# PCB-TLY-JACK-MEGA.net
KiCad netlist of a schematic drawn in EAGLE
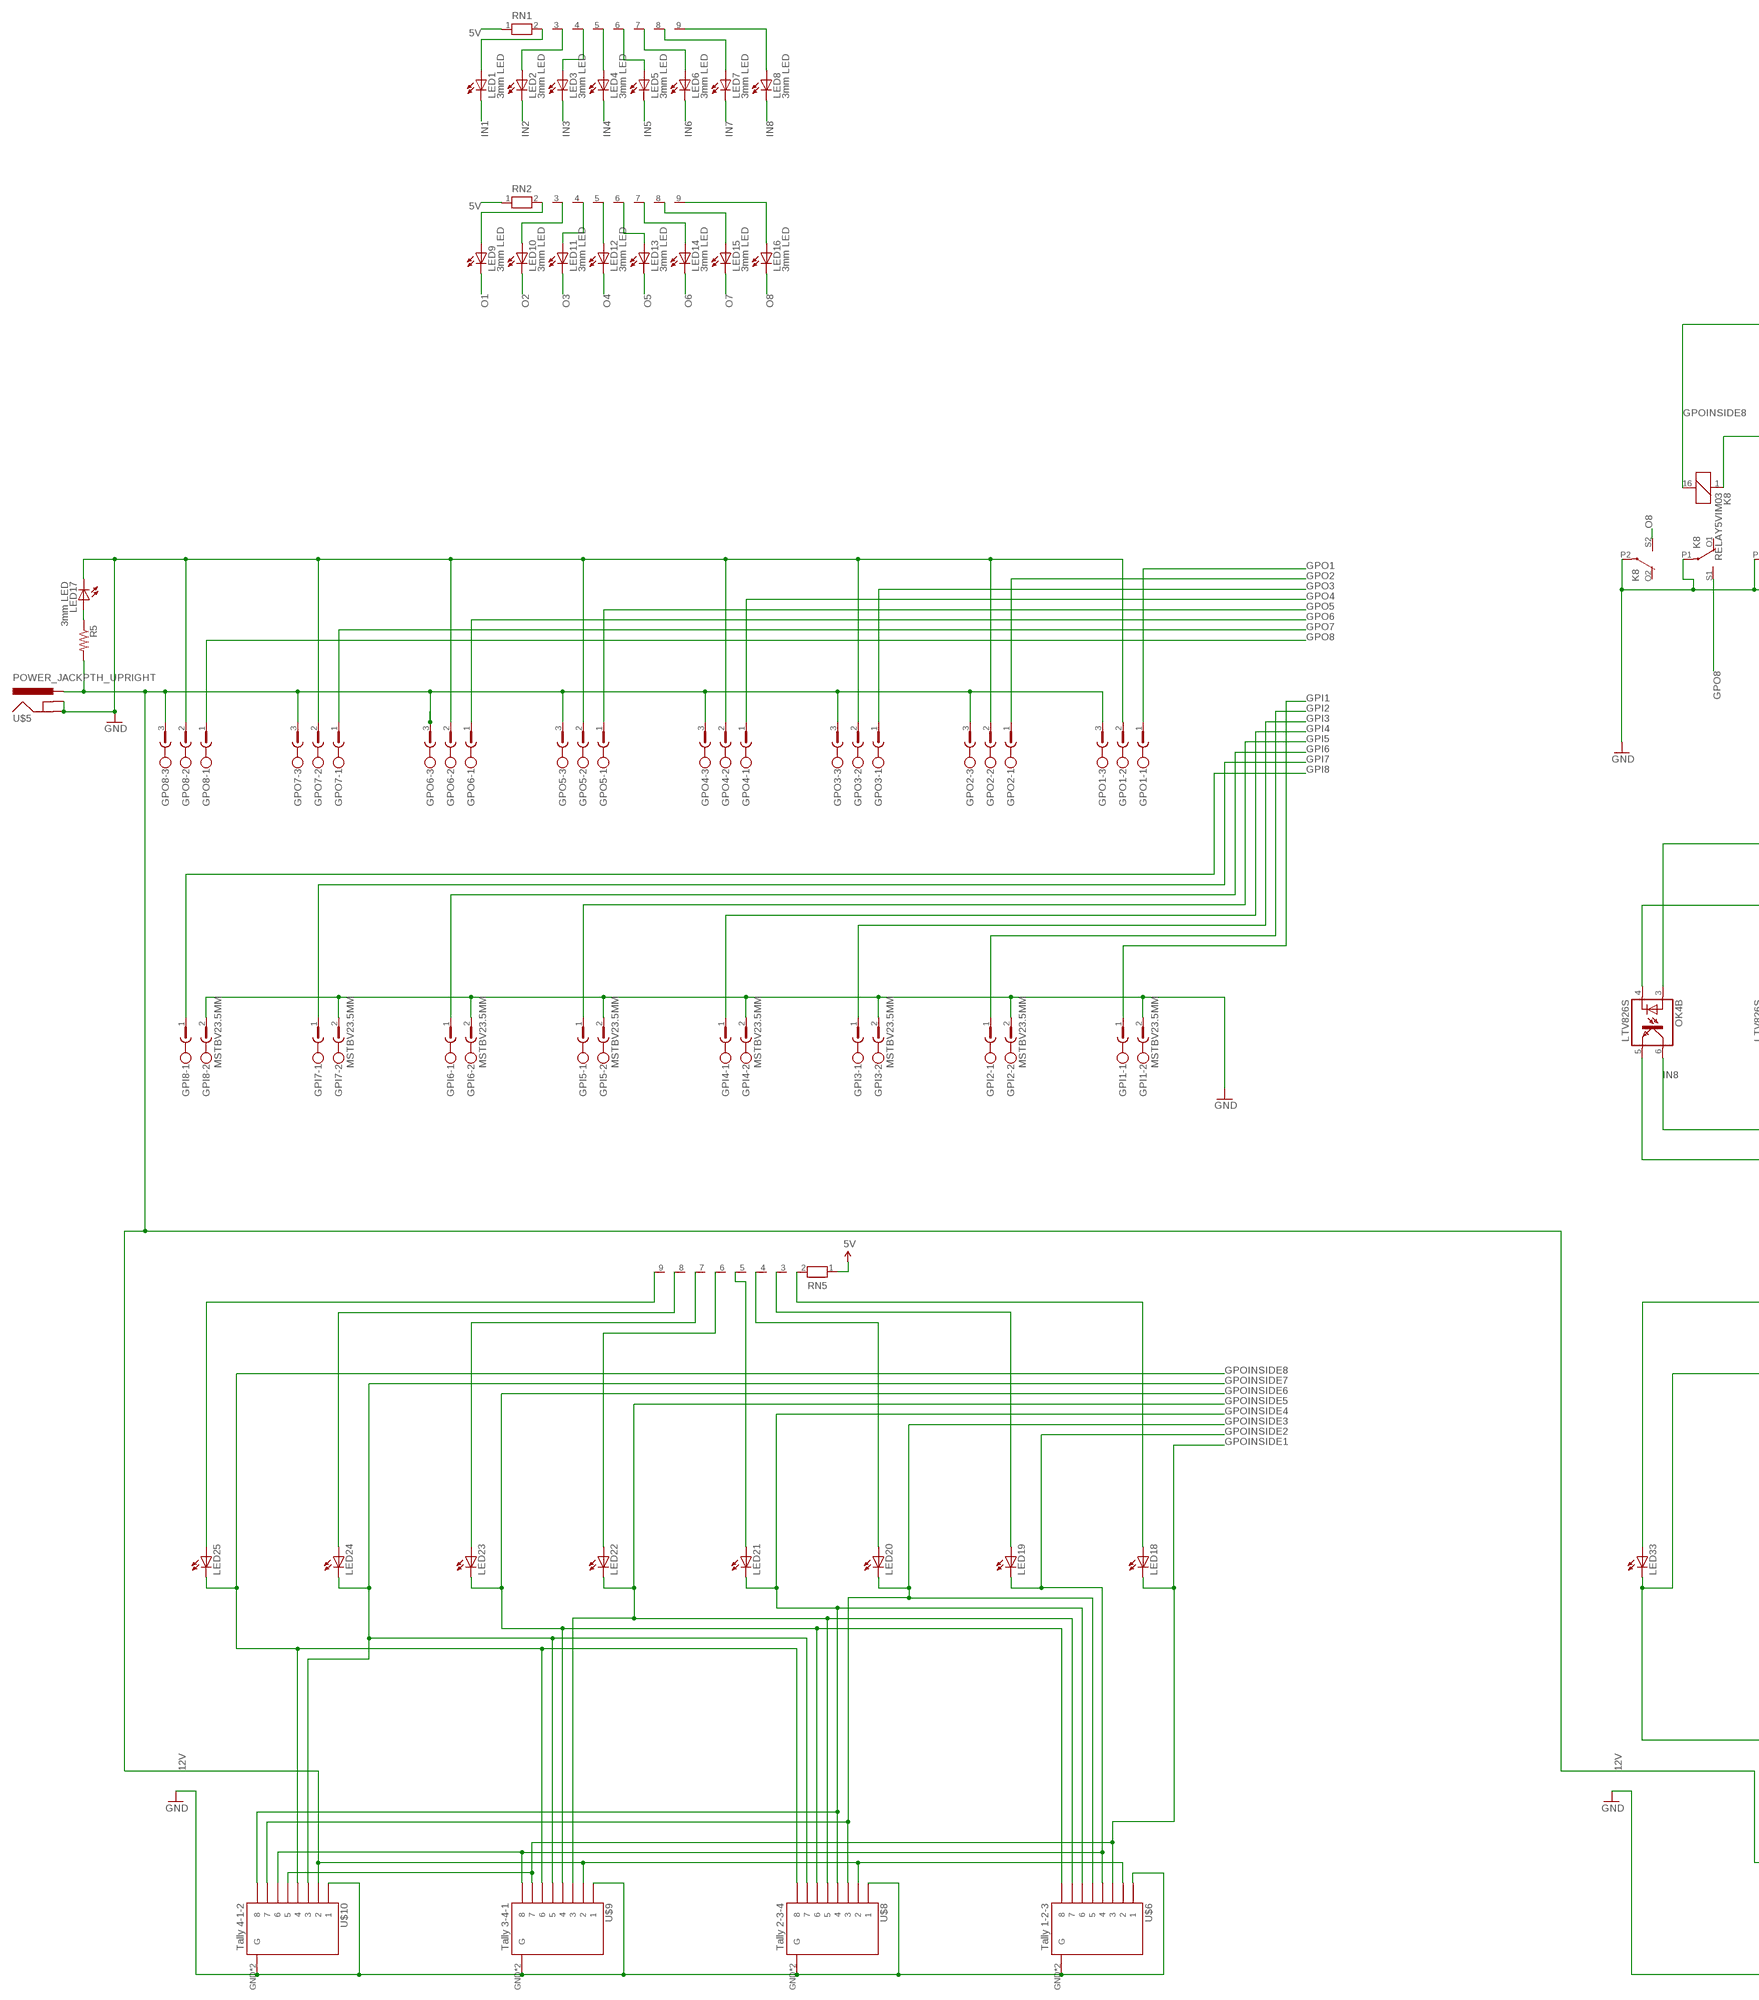
[diagram p0: schematic, sheet 1, part 1 of 2]
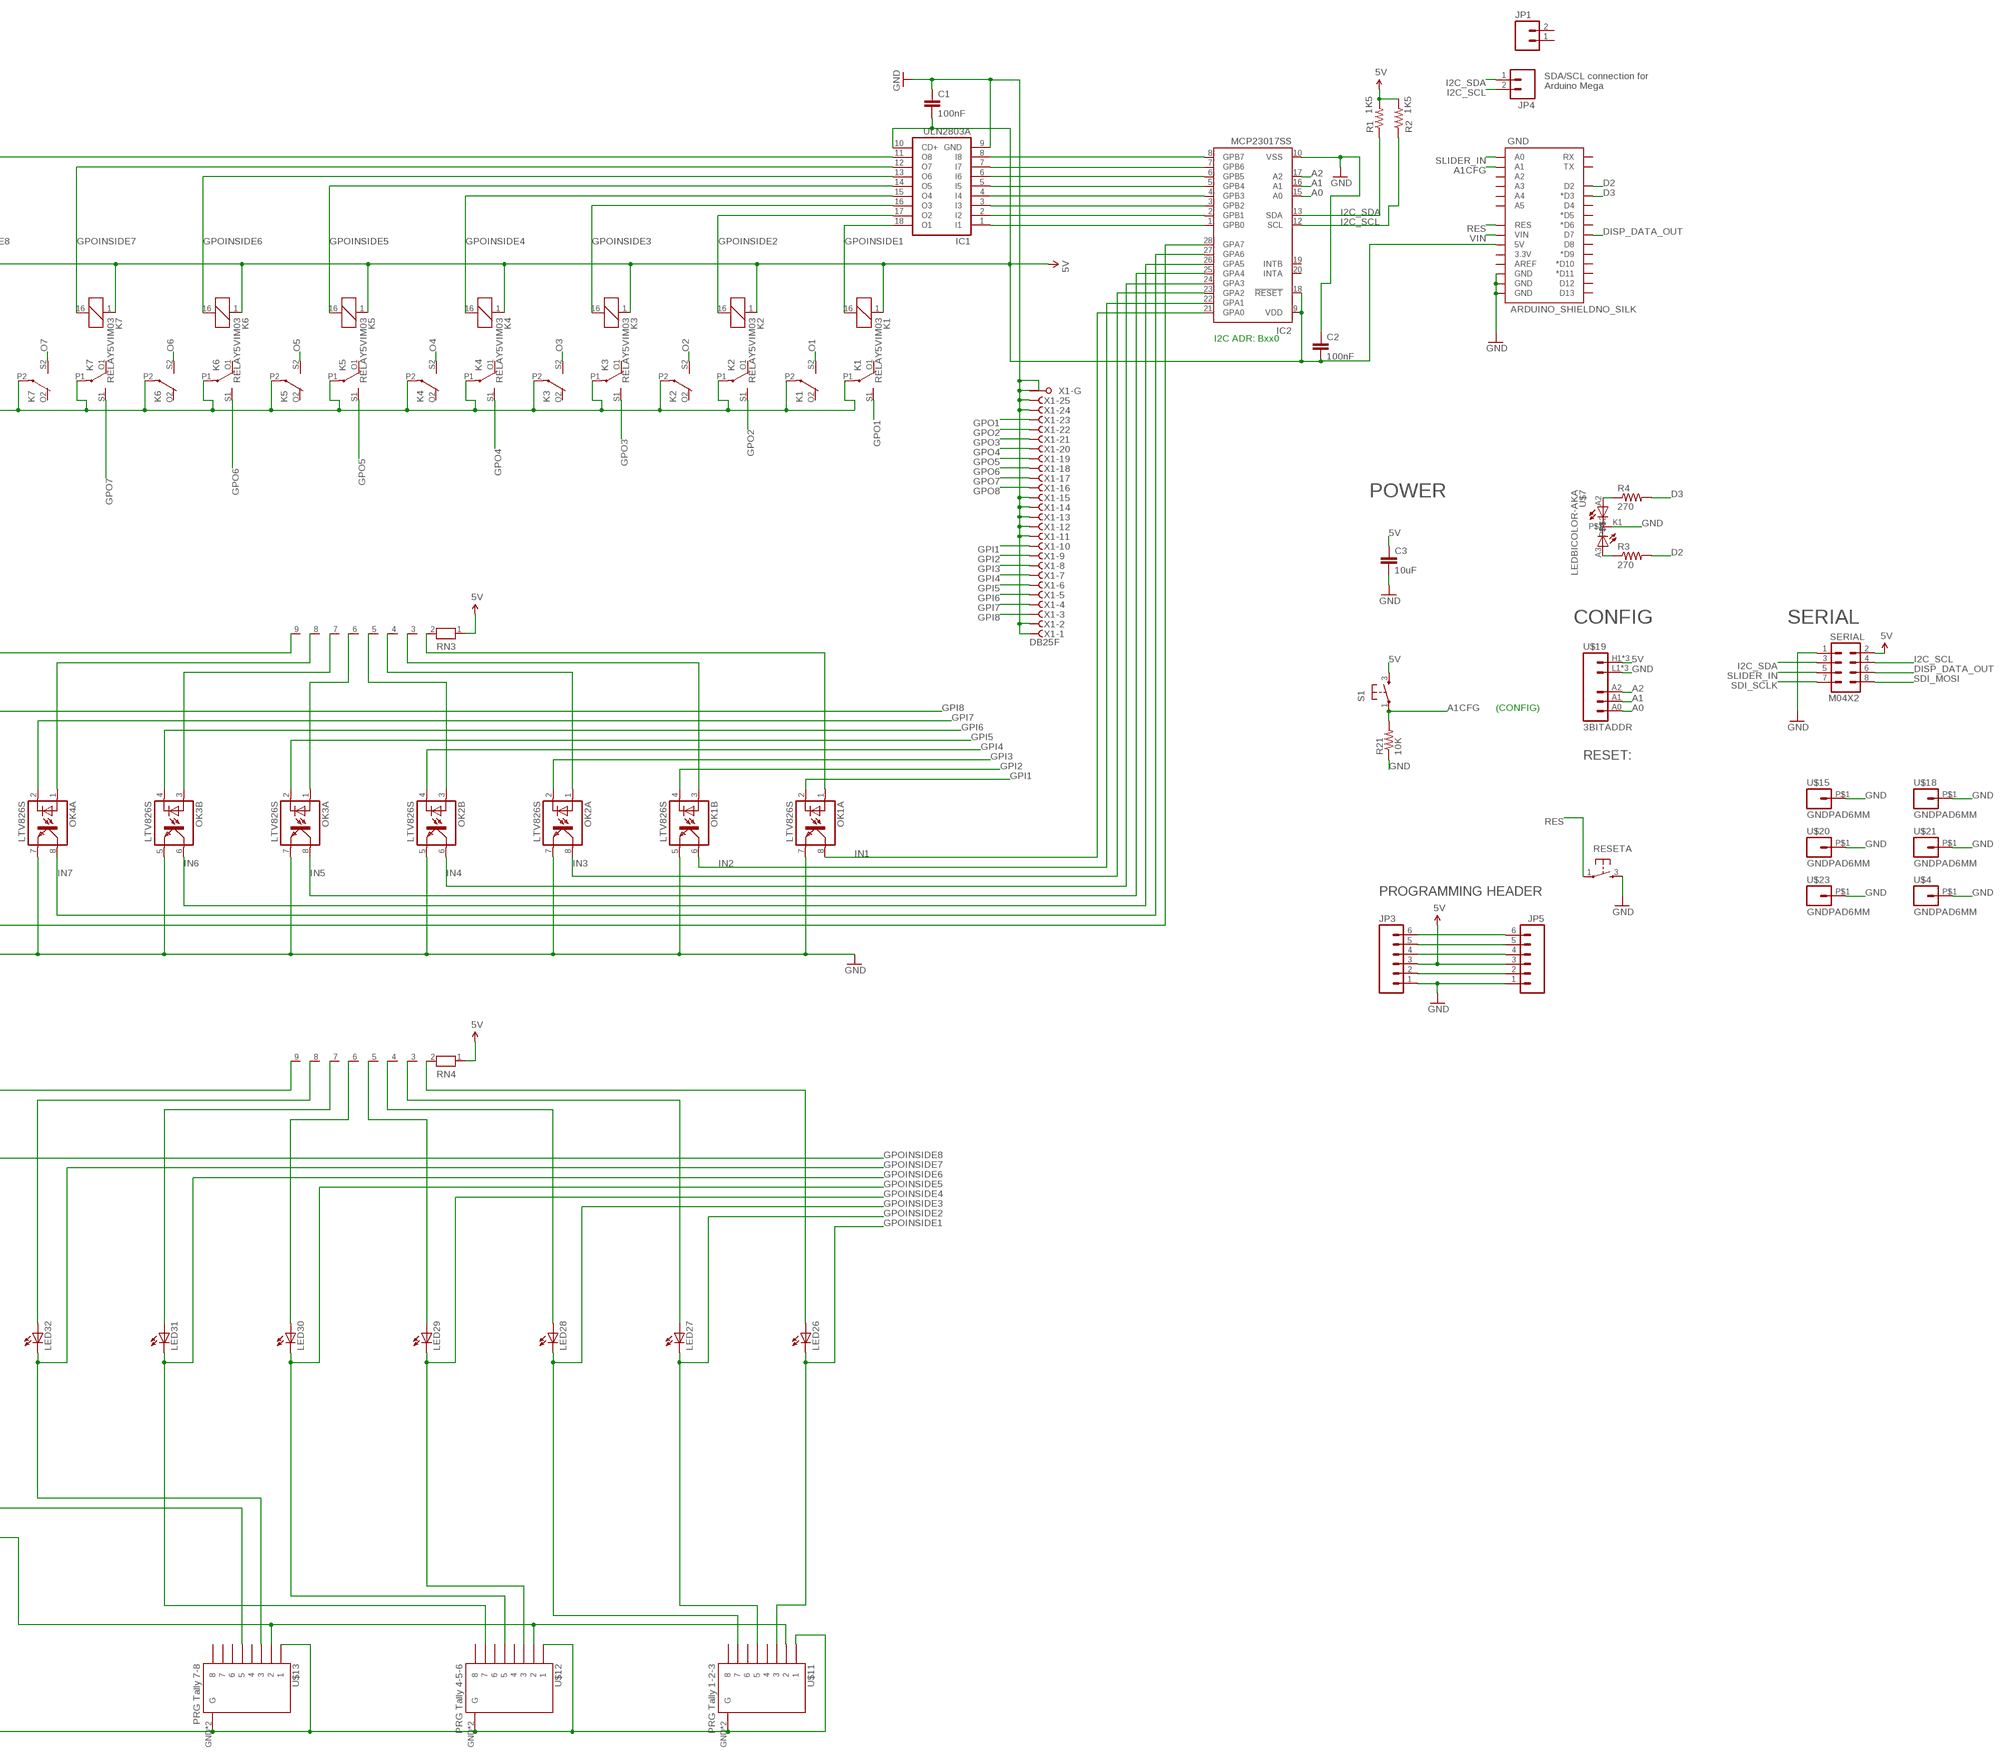
[diagram p1: schematic, sheet 1, part 2 of 2]

(export (version "E")
  (design (tool "Eeschema 10.0.6"))
  (components
    (comp (ref "C1")
      (value "100nF")
      (footprint "eagle-import:0805")
      (libsource (lib "eagle-import") (part "CAP0805"))
    )
    (comp (ref "C2")
      (value "100nF")
      (footprint "eagle-import:0603-CAP")
      (libsource (lib "eagle-import") (part "CAP0603-CAP"))
    )
    (comp (ref "C3")
      (value "10uF")
      (footprint "eagle-import:0805")
      (libsource (lib "eagle-import") (part "CAP0805"))
    )
    (comp (ref "GND")
      (value "ARDUINO_SHIELDNO_SILK")
      (footprint "eagle-import:DUEMILANOVE_VIAS")
      (libsource (lib "eagle-import") (part "ARDUINO_SHIELDNO_SILK"))
    )
    (comp (ref "GPI1")
      (value "MSTBV23.5MM")
      (footprint "eagle-import:MSTBV2-3.5")
      (libsource (lib "eagle-import") (part "MSTBV23.5MM"))
    )
    (comp (ref "GPI2")
      (value "MSTBV23.5MM")
      (footprint "eagle-import:MSTBV2-3.5")
      (libsource (lib "eagle-import") (part "MSTBV23.5MM"))
    )
    (comp (ref "GPI3")
      (value "MSTBV23.5MM")
      (footprint "eagle-import:MSTBV2-3.5")
      (libsource (lib "eagle-import") (part "MSTBV23.5MM"))
    )
    (comp (ref "GPI4")
      (value "MSTBV23.5MM")
      (footprint "eagle-import:MSTBV2-3.5")
      (libsource (lib "eagle-import") (part "MSTBV23.5MM"))
    )
    (comp (ref "GPI5")
      (value "MSTBV23.5MM")
      (footprint "eagle-import:MSTBV2-3.5")
      (libsource (lib "eagle-import") (part "MSTBV23.5MM"))
    )
    (comp (ref "GPI6")
      (value "MSTBV23.5MM")
      (footprint "eagle-import:MSTBV2-3.5")
      (libsource (lib "eagle-import") (part "MSTBV23.5MM"))
    )
    (comp (ref "GPI7")
      (value "MSTBV23.5MM")
      (footprint "eagle-import:MSTBV2-3.5")
      (libsource (lib "eagle-import") (part "MSTBV23.5MM"))
    )
    (comp (ref "GPI8")
      (value "MSTBV23.5MM")
      (footprint "eagle-import:MSTBV2-3.5")
      (libsource (lib "eagle-import") (part "MSTBV23.5MM"))
    )
    (comp (ref "GPO1")
      (value "CON1")
      (footprint "eagle-import:MSTBV3-3.5")
      (libsource (lib "eagle-import") (part "MSTBV33.5MM"))
    )
    (comp (ref "GPO2")
      (value "CON1")
      (footprint "eagle-import:MSTBV3-3.5")
      (libsource (lib "eagle-import") (part "MSTBV33.5MM"))
    )
    (comp (ref "GPO3")
      (value "CON1")
      (footprint "eagle-import:MSTBV3-3.5")
      (libsource (lib "eagle-import") (part "MSTBV33.5MM"))
    )
    (comp (ref "GPO4")
      (value "CON1")
      (footprint "eagle-import:MSTBV3-3.5")
      (libsource (lib "eagle-import") (part "MSTBV33.5MM"))
    )
    (comp (ref "GPO5")
      (value "CON1")
      (footprint "eagle-import:MSTBV3-3.5")
      (libsource (lib "eagle-import") (part "MSTBV33.5MM"))
    )
    (comp (ref "GPO6")
      (value "CON1")
      (footprint "eagle-import:MSTBV3-3.5")
      (libsource (lib "eagle-import") (part "MSTBV33.5MM"))
    )
    (comp (ref "GPO7")
      (value "CON1")
      (footprint "eagle-import:MSTBV3-3.5")
      (libsource (lib "eagle-import") (part "MSTBV33.5MM"))
    )
    (comp (ref "GPO8")
      (value "CON1")
      (footprint "eagle-import:MSTBV3-3.5")
      (libsource (lib "eagle-import") (part "MSTBV33.5MM"))
    )
    (comp (ref "IC1")
      (value "ULN2803A")
      (footprint "eagle-import:SO18W")
      (libsource (lib "eagle-import") (part "ULN2803ASO18W"))
    )
    (comp (ref "IC2")
      (value "MCP23017SS")
      (footprint "eagle-import:SSOP28")
      (fields (field (name "MF") "MICROCHIP") (field (name "MPN") "MCP23017-E/SS"))
      (libsource (lib "eagle-import") (part "MCP23017SS"))
    )
    (comp (ref "JP1")
      (value "M02PTH")
      (footprint "eagle-import:1X02")
      (libsource (lib "eagle-import") (part "M02PTH"))
    )
    (comp (ref "JP3")
      (value "M06POLAR")
      (footprint "eagle-import:MOLEX-1X6")
      (libsource (lib "eagle-import") (part "M06POLAR"))
    )
    (comp (ref "JP4")
      (value "M02PTH")
      (footprint "eagle-import:1X02")
      (libsource (lib "eagle-import") (part "M02PTH"))
    )
    (comp (ref "JP5")
      (value "M06POLAR")
      (footprint "eagle-import:MOLEX-1X6")
      (libsource (lib "eagle-import") (part "M06POLAR"))
    )
    (comp (ref "K1")
      (value "RELAY5VIM03")
      (footprint "eagle-import:DS2Y")
      (libsource (lib "eagle-import") (part "RELAY5VIM03"))
    )
    (comp (ref "K2")
      (value "RELAY5VIM03")
      (footprint "eagle-import:DS2Y")
      (libsource (lib "eagle-import") (part "RELAY5VIM03"))
    )
    (comp (ref "K3")
      (value "RELAY5VIM03")
      (footprint "eagle-import:DS2Y")
      (libsource (lib "eagle-import") (part "RELAY5VIM03"))
    )
    (comp (ref "K4")
      (value "RELAY5VIM03")
      (footprint "eagle-import:DS2Y")
      (libsource (lib "eagle-import") (part "RELAY5VIM03"))
    )
    (comp (ref "K5")
      (value "RELAY5VIM03")
      (footprint "eagle-import:DS2Y")
      (libsource (lib "eagle-import") (part "RELAY5VIM03"))
    )
    (comp (ref "K6")
      (value "RELAY5VIM03")
      (footprint "eagle-import:DS2Y")
      (libsource (lib "eagle-import") (part "RELAY5VIM03"))
    )
    (comp (ref "K7")
      (value "RELAY5VIM03")
      (footprint "eagle-import:DS2Y")
      (libsource (lib "eagle-import") (part "RELAY5VIM03"))
    )
    (comp (ref "K8")
      (value "RELAY5VIM03")
      (footprint "eagle-import:DS2Y")
      (libsource (lib "eagle-import") (part "RELAY5VIM03"))
    )
    (comp (ref "LED1")
      (value "3mm LED")
      (footprint "eagle-import:LED3MM")
      (libsource (lib "eagle-import") (part "LED3MM"))
    )
    (comp (ref "LED2")
      (value "3mm LED")
      (footprint "eagle-import:LED3MM")
      (libsource (lib "eagle-import") (part "LED3MM"))
    )
    (comp (ref "LED3")
      (value "3mm LED")
      (footprint "eagle-import:LED3MM")
      (libsource (lib "eagle-import") (part "LED3MM"))
    )
    (comp (ref "LED4")
      (value "3mm LED")
      (footprint "eagle-import:LED3MM")
      (libsource (lib "eagle-import") (part "LED3MM"))
    )
    (comp (ref "LED5")
      (value "3mm LED")
      (footprint "eagle-import:LED3MM")
      (libsource (lib "eagle-import") (part "LED3MM"))
    )
    (comp (ref "LED6")
      (value "3mm LED")
      (footprint "eagle-import:LED3MM")
      (libsource (lib "eagle-import") (part "LED3MM"))
    )
    (comp (ref "LED7")
      (value "3mm LED")
      (footprint "eagle-import:LED3MM")
      (libsource (lib "eagle-import") (part "LED3MM"))
    )
    (comp (ref "LED8")
      (value "3mm LED")
      (footprint "eagle-import:LED3MM")
      (libsource (lib "eagle-import") (part "LED3MM"))
    )
    (comp (ref "LED9")
      (value "3mm LED")
      (footprint "eagle-import:LED3MM")
      (libsource (lib "eagle-import") (part "LED3MM"))
    )
    (comp (ref "LED10")
      (value "3mm LED")
      (footprint "eagle-import:LED3MM")
      (libsource (lib "eagle-import") (part "LED3MM"))
    )
    (comp (ref "LED11")
      (value "3mm LED")
      (footprint "eagle-import:LED3MM")
      (libsource (lib "eagle-import") (part "LED3MM"))
    )
    (comp (ref "LED12")
      (value "3mm LED")
      (footprint "eagle-import:LED3MM")
      (libsource (lib "eagle-import") (part "LED3MM"))
    )
    (comp (ref "LED13")
      (value "3mm LED")
      (footprint "eagle-import:LED3MM")
      (libsource (lib "eagle-import") (part "LED3MM"))
    )
    (comp (ref "LED14")
      (value "3mm LED")
      (footprint "eagle-import:LED3MM")
      (libsource (lib "eagle-import") (part "LED3MM"))
    )
    (comp (ref "LED15")
      (value "3mm LED")
      (footprint "eagle-import:LED3MM")
      (libsource (lib "eagle-import") (part "LED3MM"))
    )
    (comp (ref "LED16")
      (value "3mm LED")
      (footprint "eagle-import:LED3MM")
      (libsource (lib "eagle-import") (part "LED3MM"))
    )
    (comp (ref "LED17")
      (value "3mm LED")
      (footprint "eagle-import:LED3MM")
      (libsource (lib "eagle-import") (part "LED3MM"))
    )
    (comp (ref "LED18")
      (value "LED3MM")
      (footprint "eagle-import:LED3MM")
      (libsource (lib "eagle-import") (part "led_LED3MM"))
    )
    (comp (ref "LED19")
      (value "LED3MM")
      (footprint "eagle-import:LED3MM")
      (libsource (lib "eagle-import") (part "led_LED3MM"))
    )
    (comp (ref "LED20")
      (value "LED3MM")
      (footprint "eagle-import:LED3MM")
      (libsource (lib "eagle-import") (part "led_LED3MM"))
    )
    (comp (ref "LED21")
      (value "LED3MM")
      (footprint "eagle-import:LED3MM")
      (libsource (lib "eagle-import") (part "led_LED3MM"))
    )
    (comp (ref "LED22")
      (value "LED3MM")
      (footprint "eagle-import:LED3MM")
      (libsource (lib "eagle-import") (part "led_LED3MM"))
    )
    (comp (ref "LED23")
      (value "LED3MM")
      (footprint "eagle-import:LED3MM")
      (libsource (lib "eagle-import") (part "led_LED3MM"))
    )
    (comp (ref "LED24")
      (value "LED3MM")
      (footprint "eagle-import:LED3MM")
      (libsource (lib "eagle-import") (part "led_LED3MM"))
    )
    (comp (ref "LED25")
      (value "LED3MM")
      (footprint "eagle-import:LED3MM")
      (libsource (lib "eagle-import") (part "led_LED3MM"))
    )
    (comp (ref "LED26")
      (value "LED3MM")
      (footprint "eagle-import:LED3MM")
      (libsource (lib "eagle-import") (part "led_LED3MM"))
    )
    (comp (ref "LED27")
      (value "LED3MM")
      (footprint "eagle-import:LED3MM")
      (libsource (lib "eagle-import") (part "led_LED3MM"))
    )
    (comp (ref "LED28")
      (value "LED3MM")
      (footprint "eagle-import:LED3MM")
      (libsource (lib "eagle-import") (part "led_LED3MM"))
    )
    (comp (ref "LED29")
      (value "LED3MM")
      (footprint "eagle-import:LED3MM")
      (libsource (lib "eagle-import") (part "led_LED3MM"))
    )
    (comp (ref "LED30")
      (value "LED3MM")
      (footprint "eagle-import:LED3MM")
      (libsource (lib "eagle-import") (part "led_LED3MM"))
    )
    (comp (ref "LED31")
      (value "LED3MM")
      (footprint "eagle-import:LED3MM")
      (libsource (lib "eagle-import") (part "led_LED3MM"))
    )
    (comp (ref "LED32")
      (value "LED3MM")
      (footprint "eagle-import:LED3MM")
      (libsource (lib "eagle-import") (part "led_LED3MM"))
    )
    (comp (ref "LED33")
      (value "LED3MM")
      (footprint "eagle-import:LED3MM")
      (libsource (lib "eagle-import") (part "led_LED3MM"))
    )
    (comp (ref "OK1")
      (value "LTV826S")
      (footprint "eagle-import:DIL8-SMD")
      (libsource (lib "eagle-import") (part "LTV826S"))
    )
    (comp (ref "OK2")
      (value "LTV826S")
      (footprint "eagle-import:DIL8-SMD")
      (libsource (lib "eagle-import") (part "LTV826S"))
    )
    (comp (ref "OK3")
      (value "LTV826S")
      (footprint "eagle-import:DIL8-SMD")
      (libsource (lib "eagle-import") (part "LTV826S"))
    )
    (comp (ref "OK4")
      (value "LTV826S")
      (footprint "eagle-import:DIL8-SMD")
      (libsource (lib "eagle-import") (part "LTV826S"))
    )
    (comp (ref "R1")
      (value "1K5")
      (footprint "eagle-import:0603-RES")
      (libsource (lib "eagle-import") (part "RESISTOR0603-RES"))
    )
    (comp (ref "R2")
      (value "1K5")
      (footprint "eagle-import:0603-RES")
      (libsource (lib "eagle-import") (part "RESISTOR0603-RES"))
    )
    (comp (ref "R3")
      (value "270")
      (footprint "eagle-import:0603-RES")
      (libsource (lib "eagle-import") (part "RESISTOR0603-RES"))
    )
    (comp (ref "R4")
      (value "270")
      (footprint "eagle-import:0603-RES")
      (libsource (lib "eagle-import") (part "RESISTOR0603-RES"))
    )
    (comp (ref "R5")
      (value "RESISTOR0603-RES")
      (footprint "eagle-import:0603-RES")
      (libsource (lib "eagle-import") (part "RESISTOR0603-RES"))
    )
    (comp (ref "R21")
      (value "10K")
      (footprint "eagle-import:0603-RES")
      (libsource (lib "eagle-import") (part "RESISTOR0603-RES"))
    )
    (comp (ref "RESETA")
      (value "TAC_SWITCH")
      (footprint "eagle-import:PUSHBUTTON")
      (libsource (lib "eagle-import") (part "TAC_SWITCH"))
    )
    (comp (ref "RN1")
      (value "RN08")
      (footprint "eagle-import:RN-9")
      (libsource (lib "eagle-import") (part "RN08"))
    )
    (comp (ref "RN2")
      (value "RN08")
      (footprint "eagle-import:RN-9")
      (libsource (lib "eagle-import") (part "RN08"))
    )
    (comp (ref "RN3")
      (value "RN08")
      (footprint "eagle-import:RN-9")
      (libsource (lib "eagle-import") (part "RN08"))
    )
    (comp (ref "RN4")
      (value "RN08")
      (footprint "eagle-import:RN-9")
      (libsource (lib "eagle-import") (part "RN08"))
    )
    (comp (ref "RN5")
      (value "RN08")
      (footprint "eagle-import:RN-9")
      (libsource (lib "eagle-import") (part "RN08"))
    )
    (comp (ref "S1")
      (value "TAC_SWITCH")
      (footprint "eagle-import:PUSHBUTTON")
      (libsource (lib "eagle-import") (part "TAC_SWITCH"))
    )
    (comp (ref "SERIAL")
      (value "M04X2")
      (footprint "eagle-import:2X4")
      (libsource (lib "eagle-import") (part "M04X2"))
    )
    (comp (ref "U$4")
      (value "GNDPAD6MM")
      (footprint "eagle-import:3.2MMPAD6MM")
      (libsource (lib "eagle-import") (part "GNDPAD6MM"))
    )
    (comp (ref "U$5")
      (value "POWER_JACKPTH_UPRIGHT")
      (footprint "eagle-import:POWER_JACK_PTH_UPRIGHT")
      (libsource (lib "eagle-import") (part "POWER_JACKPTH_UPRIGHT"))
    )
    (comp (ref "U$6")
      (value "Tally 1-2-3")
      (footprint "eagle-import:RJ45-8_GND_UPRIGHT")
      (libsource (lib "eagle-import") (part "RJ45-8_GNDUPRIGHT"))
    )
    (comp (ref "U$7")
      (value "LEDBICOLOR-AKA")
      (footprint "eagle-import:LED5MM-BICOLOR")
      (libsource (lib "eagle-import") (part "LEDBICOLOR-AKA"))
    )
    (comp (ref "U$8")
      (value "Tally 2-3-4")
      (footprint "eagle-import:RJ45-8_GND_UPRIGHT")
      (libsource (lib "eagle-import") (part "RJ45-8_GNDUPRIGHT"))
    )
    (comp (ref "U$9")
      (value "Tally 3-4-1")
      (footprint "eagle-import:RJ45-8_GND_UPRIGHT")
      (libsource (lib "eagle-import") (part "RJ45-8_GNDUPRIGHT"))
    )
    (comp (ref "U$10")
      (value "Tally 4-1-2")
      (footprint "eagle-import:RJ45-8_GND_UPRIGHT")
      (libsource (lib "eagle-import") (part "RJ45-8_GNDUPRIGHT"))
    )
    (comp (ref "U$11")
      (value "PRG Tally 1-2-3")
      (footprint "eagle-import:RJ45-8_GND_UPRIGHT")
      (libsource (lib "eagle-import") (part "RJ45-8_GNDUPRIGHT"))
    )
    (comp (ref "U$12")
      (value "PRG Tally 4-5-6")
      (footprint "eagle-import:RJ45-8_GND_UPRIGHT")
      (libsource (lib "eagle-import") (part "RJ45-8_GNDUPRIGHT"))
    )
    (comp (ref "U$13")
      (value "PRG Tally 7-8")
      (footprint "eagle-import:RJ45-8_GND_UPRIGHT")
      (libsource (lib "eagle-import") (part "RJ45-8_GNDUPRIGHT"))
    )
    (comp (ref "U$15")
      (value "GNDPAD6MM")
      (footprint "eagle-import:3.2MMPAD6MM")
      (libsource (lib "eagle-import") (part "GNDPAD6MM"))
    )
    (comp (ref "U$18")
      (value "GNDPAD6MM")
      (footprint "eagle-import:3.2MMPAD6MM")
      (libsource (lib "eagle-import") (part "GNDPAD6MM"))
    )
    (comp (ref "U$19")
      (value "3BITADDR")
      (footprint "eagle-import:3BITADDR")
      (libsource (lib "eagle-import") (part "3BITADDR"))
    )
    (comp (ref "U$20")
      (value "GNDPAD6MM")
      (footprint "eagle-import:3.2MMPAD6MM")
      (libsource (lib "eagle-import") (part "GNDPAD6MM"))
    )
    (comp (ref "U$21")
      (value "GNDPAD6MM")
      (footprint "eagle-import:3.2MMPAD6MM")
      (libsource (lib "eagle-import") (part "GNDPAD6MM"))
    )
    (comp (ref "U$23")
      (value "GNDPAD6MM")
      (footprint "eagle-import:3.2MMPAD6MM")
      (libsource (lib "eagle-import") (part "GNDPAD6MM"))
    )
    (comp (ref "X1")
      (value "DB25F")
      (footprint "eagle-import:F25HP")
      (libsource (lib "eagle-import") (part "F25HPS"))
    )
  )
  (nets
    (net (code "1") (name "5V") (class "Default")
      (node (ref "C1") (pin "2") (pinfunction "2_2") (pintype "passive"))
      (node (ref "C2") (pin "2") (pinfunction "2_2") (pintype "passive"))
      (node (ref "C3") (pin "1") (pinfunction "1_1") (pintype "passive"))
      (node (ref "GND") (pin "5V") (pinfunction "5V_5V") (pintype "bidirectional"))
      (node (ref "IC1") (pin "10") (pinfunction "CD+_10") (pintype "passive"))
      (node (ref "IC2") (pin "18") (pinfunction "~{RESET}_18") (pintype "input"))
      (node (ref "IC2") (pin "9") (pinfunction "VDD_9") (pintype "power_in"))
      (node (ref "JP3") (pin "3") (pinfunction "3_3") (pintype "passive"))
      (node (ref "JP5") (pin "3") (pinfunction "3_3") (pintype "passive"))
      (node (ref "K1") (pin "1") (pinfunction "1_1") (pintype "passive"))
      (node (ref "K2") (pin "1") (pinfunction "1_1") (pintype "passive"))
      (node (ref "K3") (pin "1") (pinfunction "1_1") (pintype "passive"))
      (node (ref "K4") (pin "1") (pinfunction "1_1") (pintype "passive"))
      (node (ref "K5") (pin "1") (pinfunction "1_1") (pintype "passive"))
      (node (ref "K6") (pin "1") (pinfunction "1_1") (pintype "passive"))
      (node (ref "K7") (pin "1") (pinfunction "1_1") (pintype "passive"))
      (node (ref "K8") (pin "1") (pinfunction "1_1") (pintype "passive"))
      (node (ref "R1") (pin "2") (pinfunction "2_2") (pintype "passive"))
      (node (ref "R2") (pin "2") (pinfunction "2_2") (pintype "passive"))
      (node (ref "RN1") (pin "1") (pinfunction "1_1") (pintype "passive"))
      (node (ref "RN2") (pin "1") (pinfunction "1_1") (pintype "passive"))
      (node (ref "RN3") (pin "1") (pinfunction "1_1") (pintype "passive"))
      (node (ref "RN4") (pin "1") (pinfunction "1_1") (pintype "passive"))
      (node (ref "RN5") (pin "1") (pinfunction "1_1") (pintype "passive"))
      (node (ref "S1") (pin "3") (pinfunction "3_3") (pintype "passive"))
      (node (ref "SERIAL") (pin "2") (pinfunction "2_2") (pintype "passive"))
      (node (ref "U$19") (pin "H1") (pinfunction "VCC_H1") (pintype "passive"))
      (node (ref "U$19") (pin "H2") (pinfunction "VCC_H2") (pintype "passive"))
      (node (ref "U$19") (pin "H3") (pinfunction "VCC_H3") (pintype "passive"))
    )
    (net (code "2") (name "12V") (class "Default")
      (node (ref "GPO1") (pin "3") (pinfunction "1_3") (pintype "passive"))
      (node (ref "GPO2") (pin "3") (pinfunction "1_3") (pintype "passive"))
      (node (ref "GPO3") (pin "3") (pinfunction "1_3") (pintype "passive"))
      (node (ref "GPO4") (pin "3") (pinfunction "1_3") (pintype "passive"))
      (node (ref "GPO5") (pin "3") (pinfunction "1_3") (pintype "passive"))
      (node (ref "GPO6") (pin "3") (pinfunction "1_3") (pintype "passive"))
      (node (ref "GPO7") (pin "3") (pinfunction "1_3") (pintype "passive"))
      (node (ref "GPO8") (pin "3") (pinfunction "1_3") (pintype "passive"))
      (node (ref "R5") (pin "2") (pinfunction "2_2") (pintype "passive"))
      (node (ref "U$10") (pin "2") (pinfunction "2_2") (pintype "bidirectional"))
      (node (ref "U$11") (pin "2") (pinfunction "2_2") (pintype "bidirectional"))
      (node (ref "U$12") (pin "2") (pinfunction "2_2") (pintype "bidirectional"))
      (node (ref "U$13") (pin "2") (pinfunction "2_2") (pintype "bidirectional"))
      (node (ref "U$5") (pin "PWR") (pinfunction "PWR_PWR") (pintype "bidirectional"))
      (node (ref "U$6") (pin "2") (pinfunction "2_2") (pintype "bidirectional"))
      (node (ref "U$8") (pin "2") (pinfunction "2_2") (pintype "bidirectional"))
      (node (ref "U$9") (pin "2") (pinfunction "2_2") (pintype "bidirectional"))
    )
    (net (code "3") (name "A0") (class "Default")
      (node (ref "IC2") (pin "15") (pinfunction "A0_15") (pintype "input"))
      (node (ref "U$19") (pin "A0") (pinfunction "A0_A0") (pintype "passive"))
    )
    (net (code "4") (name "A1") (class "Default")
      (node (ref "IC2") (pin "16") (pinfunction "A1_16") (pintype "input"))
      (node (ref "U$19") (pin "A1") (pinfunction "A1_A1") (pintype "passive"))
    )
    (net (code "5") (name "A1CFG") (class "Default")
      (node (ref "GND") (pin "A1") (pinfunction "A1_A1") (pintype "bidirectional"))
      (node (ref "R21") (pin "2") (pinfunction "2_2") (pintype "passive"))
      (node (ref "S1") (pin "1") (pinfunction "1_1") (pintype "passive"))
    )
    (net (code "6") (name "A2") (class "Default")
      (node (ref "IC2") (pin "17") (pinfunction "A2_17") (pintype "input"))
      (node (ref "U$19") (pin "A2") (pinfunction "A2_A2") (pintype "passive"))
    )
    (net (code "7") (name "D2") (class "Default")
      (node (ref "GND") (pin "D2") (pinfunction "D2_D2") (pintype "bidirectional"))
      (node (ref "R3") (pin "2") (pinfunction "2_2") (pintype "passive"))
    )
    (net (code "8") (name "D3") (class "Default")
      (node (ref "GND") (pin "D3") (pinfunction "*D3_D3") (pintype "bidirectional"))
      (node (ref "R4") (pin "2") (pinfunction "2_2") (pintype "passive"))
    )
    (net (code "9") (name "DISP_DATA_OUT") (class "Default")
      (node (ref "GND") (pin "D7") (pinfunction "D7_D7") (pintype "bidirectional"))
      (node (ref "SERIAL") (pin "6") (pinfunction "6_6") (pintype "passive"))
    )
    (net (code "10") (name "GND") (class "Default")
      (node (ref "C1") (pin "1") (pinfunction "1_1") (pintype "passive"))
      (node (ref "C2") (pin "1") (pinfunction "1_1") (pintype "passive"))
      (node (ref "C3") (pin "2") (pinfunction "2_2") (pintype "passive"))
      (node (ref "GND") (pin "GND@0") (pinfunction "GND_GND@0") (pintype "bidirectional"))
      (node (ref "GND") (pin "GND@1") (pinfunction "GND_GND@1") (pintype "bidirectional"))
      (node (ref "GND") (pin "GND@2") (pinfunction "GND_GND@2") (pintype "bidirectional"))
      (node (ref "GPI1") (pin "2") (pinfunction "1_2") (pintype "passive"))
      (node (ref "GPI2") (pin "2") (pinfunction "1_2") (pintype "passive"))
      (node (ref "GPI3") (pin "2") (pinfunction "1_2") (pintype "passive"))
      (node (ref "GPI4") (pin "2") (pinfunction "1_2") (pintype "passive"))
      (node (ref "GPI5") (pin "2") (pinfunction "1_2") (pintype "passive"))
      (node (ref "GPI6") (pin "2") (pinfunction "1_2") (pintype "passive"))
      (node (ref "GPI7") (pin "2") (pinfunction "1_2") (pintype "passive"))
      (node (ref "GPI8") (pin "2") (pinfunction "1_2") (pintype "passive"))
      (node (ref "GPO1") (pin "2") (pinfunction "1_2") (pintype "passive"))
      (node (ref "GPO2") (pin "2") (pinfunction "1_2") (pintype "passive"))
      (node (ref "GPO3") (pin "2") (pinfunction "1_2") (pintype "passive"))
      (node (ref "GPO4") (pin "2") (pinfunction "1_2") (pintype "passive"))
      (node (ref "GPO5") (pin "2") (pinfunction "1_2") (pintype "passive"))
      (node (ref "GPO6") (pin "2") (pinfunction "1_2") (pintype "passive"))
      (node (ref "GPO7") (pin "2") (pinfunction "1_2") (pintype "passive"))
      (node (ref "GPO8") (pin "2") (pinfunction "1_2") (pintype "passive"))
      (node (ref "IC1") (pin "9") (pinfunction "GND_9") (pintype "power_in"))
      (node (ref "IC2") (pin "10") (pinfunction "VSS_10") (pintype "power_in"))
      (node (ref "JP3") (pin "1") (pinfunction "1_1") (pintype "passive"))
      (node (ref "JP5") (pin "1") (pinfunction "1_1") (pintype "passive"))
      (node (ref "K1") (pin "P1") (pinfunction "P_P1") (pintype "passive"))
      (node (ref "K1") (pin "P2") (pinfunction "P_P2") (pintype "passive"))
      (node (ref "K2") (pin "P1") (pinfunction "P_P1") (pintype "passive"))
      (node (ref "K2") (pin "P2") (pinfunction "P_P2") (pintype "passive"))
      (node (ref "K3") (pin "P1") (pinfunction "P_P1") (pintype "passive"))
      (node (ref "K3") (pin "P2") (pinfunction "P_P2") (pintype "passive"))
      (node (ref "K4") (pin "P1") (pinfunction "P_P1") (pintype "passive"))
      (node (ref "K4") (pin "P2") (pinfunction "P_P2") (pintype "passive"))
      (node (ref "K5") (pin "P1") (pinfunction "P_P1") (pintype "passive"))
      (node (ref "K5") (pin "P2") (pinfunction "P_P2") (pintype "passive"))
      (node (ref "K6") (pin "P1") (pinfunction "P_P1") (pintype "passive"))
      (node (ref "K6") (pin "P2") (pinfunction "P_P2") (pintype "passive"))
      (node (ref "K7") (pin "P1") (pinfunction "P_P1") (pintype "passive"))
      (node (ref "K7") (pin "P2") (pinfunction "P_P2") (pintype "passive"))
      (node (ref "K8") (pin "P1") (pinfunction "P_P1") (pintype "passive"))
      (node (ref "K8") (pin "P2") (pinfunction "P_P2") (pintype "passive"))
      (node (ref "LED17") (pin "K") (pinfunction "C_K") (pintype "passive"))
      (node (ref "OK1") (pin "5") (pinfunction "EMIT_5") (pintype "passive"))
      (node (ref "OK1") (pin "7") (pinfunction "EMIT_7") (pintype "passive"))
      (node (ref "OK2") (pin "5") (pinfunction "EMIT_5") (pintype "passive"))
      (node (ref "OK2") (pin "7") (pinfunction "EMIT_7") (pintype "passive"))
      (node (ref "OK3") (pin "5") (pinfunction "EMIT_5") (pintype "passive"))
      (node (ref "OK3") (pin "7") (pinfunction "EMIT_7") (pintype "passive"))
      (node (ref "OK4") (pin "5") (pinfunction "EMIT_5") (pintype "passive"))
      (node (ref "OK4") (pin "7") (pinfunction "EMIT_7") (pintype "passive"))
      (node (ref "R21") (pin "1") (pinfunction "1_1") (pintype "passive"))
      (node (ref "RESETA") (pin "3") (pinfunction "3_3") (pintype "passive"))
      (node (ref "SERIAL") (pin "1") (pinfunction "1_1") (pintype "passive"))
      (node (ref "U$10") (pin "1") (pinfunction "1_1") (pintype "bidirectional"))
      (node (ref "U$10") (pin "GND") (pinfunction "G_GND") (pintype "power_in"))
      (node (ref "U$10") (pin "GND1") (pinfunction "G_GND1") (pintype "power_in"))
      (node (ref "U$11") (pin "1") (pinfunction "1_1") (pintype "bidirectional"))
      (node (ref "U$11") (pin "GND") (pinfunction "G_GND") (pintype "power_in"))
      (node (ref "U$11") (pin "GND1") (pinfunction "G_GND1") (pintype "power_in"))
      (node (ref "U$12") (pin "1") (pinfunction "1_1") (pintype "bidirectional"))
      (node (ref "U$12") (pin "GND") (pinfunction "G_GND") (pintype "power_in"))
      (node (ref "U$12") (pin "GND1") (pinfunction "G_GND1") (pintype "power_in"))
      (node (ref "U$13") (pin "1") (pinfunction "1_1") (pintype "bidirectional"))
      (node (ref "U$13") (pin "GND") (pinfunction "G_GND") (pintype "power_in"))
      (node (ref "U$13") (pin "GND1") (pinfunction "G_GND1") (pintype "power_in"))
      (node (ref "U$15") (pin "P$1") (pinfunction "1_P$1") (pintype "passive"))
      (node (ref "U$18") (pin "P$1") (pinfunction "1_P$1") (pintype "passive"))
      (node (ref "U$19") (pin "L1") (pinfunction "GND_L1") (pintype "passive"))
      (node (ref "U$19") (pin "L2") (pinfunction "GND_L2") (pintype "passive"))
      (node (ref "U$19") (pin "L3") (pinfunction "GND_L3") (pintype "passive"))
      (node (ref "U$20") (pin "P$1") (pinfunction "1_P$1") (pintype "passive"))
      (node (ref "U$21") (pin "P$1") (pinfunction "1_P$1") (pintype "passive"))
      (node (ref "U$23") (pin "P$1") (pinfunction "1_P$1") (pintype "passive"))
      (node (ref "U$4") (pin "P$1") (pinfunction "1_P$1") (pintype "passive"))
      (node (ref "U$5") (pin "GND") (pinfunction "GND_GND") (pintype "bidirectional"))
      (node (ref "U$5") (pin "SHUNT") (pinfunction "GNDBREAK_SHUNT") (pintype "bidirectional"))
      (node (ref "U$6") (pin "1") (pinfunction "1_1") (pintype "bidirectional"))
      (node (ref "U$6") (pin "GND") (pinfunction "G_GND") (pintype "power_in"))
      (node (ref "U$6") (pin "GND1") (pinfunction "G_GND1") (pintype "power_in"))
      (node (ref "U$7") (pin "K1") (pinfunction "P$1_K1") (pintype "bidirectional"))
      (node (ref "U$8") (pin "1") (pinfunction "1_1") (pintype "bidirectional"))
      (node (ref "U$8") (pin "GND") (pinfunction "G_GND") (pintype "power_in"))
      (node (ref "U$8") (pin "GND1") (pinfunction "G_GND1") (pintype "power_in"))
      (node (ref "U$9") (pin "1") (pinfunction "1_1") (pintype "bidirectional"))
      (node (ref "U$9") (pin "GND") (pinfunction "G_GND") (pintype "power_in"))
      (node (ref "U$9") (pin "GND1") (pinfunction "G_GND1") (pintype "power_in"))
      (node (ref "X1") (pin "1") (pinfunction "F_1") (pintype "passive"))
      (node (ref "X1") (pin "11") (pinfunction "F_11") (pintype "passive"))
      (node (ref "X1") (pin "12") (pinfunction "F_12") (pintype "passive"))
      (node (ref "X1") (pin "13") (pinfunction "F_13") (pintype "passive"))
      (node (ref "X1") (pin "14") (pinfunction "F_14") (pintype "passive"))
      (node (ref "X1") (pin "15") (pinfunction "F_15") (pintype "passive"))
      (node (ref "X1") (pin "2") (pinfunction "F_2") (pintype "passive"))
      (node (ref "X1") (pin "24") (pinfunction "F_24") (pintype "passive"))
      (node (ref "X1") (pin "25") (pinfunction "F_25") (pintype "passive"))
      (node (ref "X1") (pin "G1") (pinfunction "G1_G1") (pintype "passive"))
      (node (ref "X1") (pin "G2") (pinfunction "G2_G2") (pintype "passive"))
    )
    (net (code "11") (name "GPI1") (class "Default")
      (node (ref "GPI1") (pin "1") (pinfunction "1_1") (pintype "passive"))
      (node (ref "OK1") (pin "2") (pinfunction "C_2") (pintype "passive"))
      (node (ref "X1") (pin "10") (pinfunction "F_10") (pintype "passive"))
    )
    (net (code "12") (name "GPI2") (class "Default")
      (node (ref "GPI2") (pin "1") (pinfunction "1_1") (pintype "passive"))
      (node (ref "OK1") (pin "4") (pinfunction "C_4") (pintype "passive"))
      (node (ref "X1") (pin "9") (pinfunction "F_9") (pintype "passive"))
    )
    (net (code "13") (name "GPI3") (class "Default")
      (node (ref "GPI3") (pin "1") (pinfunction "1_1") (pintype "passive"))
      (node (ref "OK2") (pin "2") (pinfunction "C_2") (pintype "passive"))
      (node (ref "X1") (pin "8") (pinfunction "F_8") (pintype "passive"))
    )
    (net (code "14") (name "GPI4") (class "Default")
      (node (ref "GPI4") (pin "1") (pinfunction "1_1") (pintype "passive"))
      (node (ref "OK2") (pin "4") (pinfunction "C_4") (pintype "passive"))
      (node (ref "X1") (pin "7") (pinfunction "F_7") (pintype "passive"))
    )
    (net (code "15") (name "GPI5") (class "Default")
      (node (ref "GPI5") (pin "1") (pinfunction "1_1") (pintype "passive"))
      (node (ref "OK3") (pin "2") (pinfunction "C_2") (pintype "passive"))
      (node (ref "X1") (pin "6") (pinfunction "F_6") (pintype "passive"))
    )
    (net (code "16") (name "GPI6") (class "Default")
      (node (ref "GPI6") (pin "1") (pinfunction "1_1") (pintype "passive"))
      (node (ref "OK3") (pin "4") (pinfunction "C_4") (pintype "passive"))
      (node (ref "X1") (pin "5") (pinfunction "F_5") (pintype "passive"))
    )
    (net (code "17") (name "GPI7") (class "Default")
      (node (ref "GPI7") (pin "1") (pinfunction "1_1") (pintype "passive"))
      (node (ref "OK4") (pin "2") (pinfunction "C_2") (pintype "passive"))
      (node (ref "X1") (pin "4") (pinfunction "F_4") (pintype "passive"))
    )
    (net (code "18") (name "GPI8") (class "Default")
      (node (ref "GPI8") (pin "1") (pinfunction "1_1") (pintype "passive"))
      (node (ref "OK4") (pin "4") (pinfunction "C_4") (pintype "passive"))
      (node (ref "X1") (pin "3") (pinfunction "F_3") (pintype "passive"))
    )
    (net (code "19") (name "GPO1") (class "Default")
      (node (ref "GPO1") (pin "1") (pinfunction "1_1") (pintype "passive"))
      (node (ref "K1") (pin "S1") (pinfunction "S_S1") (pintype "passive"))
      (node (ref "X1") (pin "23") (pinfunction "F_23") (pintype "passive"))
    )
    (net (code "20") (name "GPO2") (class "Default")
      (node (ref "GPO2") (pin "1") (pinfunction "1_1") (pintype "passive"))
      (node (ref "K2") (pin "S1") (pinfunction "S_S1") (pintype "passive"))
      (node (ref "X1") (pin "22") (pinfunction "F_22") (pintype "passive"))
    )
    (net (code "21") (name "GPO3") (class "Default")
      (node (ref "GPO3") (pin "1") (pinfunction "1_1") (pintype "passive"))
      (node (ref "K3") (pin "S1") (pinfunction "S_S1") (pintype "passive"))
      (node (ref "X1") (pin "21") (pinfunction "F_21") (pintype "passive"))
    )
    (net (code "22") (name "GPO4") (class "Default")
      (node (ref "GPO4") (pin "1") (pinfunction "1_1") (pintype "passive"))
      (node (ref "K4") (pin "S1") (pinfunction "S_S1") (pintype "passive"))
      (node (ref "X1") (pin "20") (pinfunction "F_20") (pintype "passive"))
    )
    (net (code "23") (name "GPO5") (class "Default")
      (node (ref "GPO5") (pin "1") (pinfunction "1_1") (pintype "passive"))
      (node (ref "K5") (pin "S1") (pinfunction "S_S1") (pintype "passive"))
      (node (ref "X1") (pin "19") (pinfunction "F_19") (pintype "passive"))
    )
    (net (code "24") (name "GPO6") (class "Default")
      (node (ref "GPO6") (pin "1") (pinfunction "1_1") (pintype "passive"))
      (node (ref "K6") (pin "S1") (pinfunction "S_S1") (pintype "passive"))
      (node (ref "X1") (pin "18") (pinfunction "F_18") (pintype "passive"))
    )
    (net (code "25") (name "GPO7") (class "Default")
      (node (ref "GPO7") (pin "1") (pinfunction "1_1") (pintype "passive"))
      (node (ref "K7") (pin "S1") (pinfunction "S_S1") (pintype "passive"))
      (node (ref "X1") (pin "17") (pinfunction "F_17") (pintype "passive"))
    )
    (net (code "26") (name "GPO8") (class "Default")
      (node (ref "GPO8") (pin "1") (pinfunction "1_1") (pintype "passive"))
      (node (ref "K8") (pin "S1") (pinfunction "S_S1") (pintype "passive"))
      (node (ref "X1") (pin "16") (pinfunction "F_16") (pintype "passive"))
    )
    (net (code "27") (name "GPOINSIDE1") (class "Default")
      (node (ref "IC1") (pin "18") (pinfunction "O1_18") (pintype "open_collector"))
      (node (ref "K1") (pin "16") (pinfunction "2_16") (pintype "passive"))
      (node (ref "LED18") (pin "K") (pinfunction "C_K") (pintype "passive"))
      (node (ref "LED26") (pin "K") (pinfunction "C_K") (pintype "passive"))
      (node (ref "U$10") (pin "5") (pinfunction "5_5") (pintype "bidirectional"))
      (node (ref "U$11") (pin "3") (pinfunction "3_3") (pintype "bidirectional"))
      (node (ref "U$6") (pin "3") (pinfunction "3_3") (pintype "bidirectional"))
      (node (ref "U$9") (pin "7") (pinfunction "7_7") (pintype "bidirectional"))
    )
    (net (code "28") (name "GPOINSIDE2") (class "Default")
      (node (ref "IC1") (pin "17") (pinfunction "O2_17") (pintype "open_collector"))
      (node (ref "K2") (pin "16") (pinfunction "2_16") (pintype "passive"))
      (node (ref "LED19") (pin "K") (pinfunction "C_K") (pintype "passive"))
      (node (ref "LED27") (pin "K") (pinfunction "C_K") (pintype "passive"))
      (node (ref "U$10") (pin "6") (pinfunction "6_6") (pintype "bidirectional"))
      (node (ref "U$11") (pin "5") (pinfunction "5_5") (pintype "bidirectional"))
      (node (ref "U$6") (pin "4") (pinfunction "4_4") (pintype "bidirectional"))
      (node (ref "U$9") (pin "8") (pinfunction "8_8") (pintype "bidirectional"))
    )
    (net (code "29") (name "GPOINSIDE3") (class "Default")
      (node (ref "IC1") (pin "16") (pinfunction "O3_16") (pintype "open_collector"))
      (node (ref "K3") (pin "16") (pinfunction "2_16") (pintype "passive"))
      (node (ref "LED20") (pin "K") (pinfunction "C_K") (pintype "passive"))
      (node (ref "LED28") (pin "K") (pinfunction "C_K") (pintype "passive"))
      (node (ref "U$10") (pin "7") (pinfunction "7_7") (pintype "bidirectional"))
      (node (ref "U$11") (pin "7") (pinfunction "7_7") (pintype "bidirectional"))
      (node (ref "U$6") (pin "5") (pinfunction "5_5") (pintype "bidirectional"))
      (node (ref "U$8") (pin "3") (pinfunction "3_3") (pintype "bidirectional"))
    )
    (net (code "30") (name "GPOINSIDE4") (class "Default")
      (node (ref "IC1") (pin "15") (pinfunction "O4_15") (pintype "open_collector"))
      (node (ref "K4") (pin "16") (pinfunction "2_16") (pintype "passive"))
      (node (ref "LED21") (pin "K") (pinfunction "C_K") (pintype "passive"))
      (node (ref "LED29") (pin "K") (pinfunction "C_K") (pintype "passive"))
      (node (ref "U$10") (pin "8") (pinfunction "8_8") (pintype "bidirectional"))
      (node (ref "U$12") (pin "3") (pinfunction "3_3") (pintype "bidirectional"))
      (node (ref "U$6") (pin "6") (pinfunction "6_6") (pintype "bidirectional"))
      (node (ref "U$8") (pin "4") (pinfunction "4_4") (pintype "bidirectional"))
    )
    (net (code "31") (name "GPOINSIDE5") (class "Default")
      (node (ref "IC1") (pin "14") (pinfunction "O5_14") (pintype "open_collector"))
      (node (ref "K5") (pin "16") (pinfunction "2_16") (pintype "passive"))
      (node (ref "LED22") (pin "K") (pinfunction "C_K") (pintype "passive"))
      (node (ref "LED30") (pin "K") (pinfunction "C_K") (pintype "passive"))
      (node (ref "U$12") (pin "5") (pinfunction "5_5") (pintype "bidirectional"))
      (node (ref "U$6") (pin "7") (pinfunction "7_7") (pintype "bidirectional"))
      (node (ref "U$8") (pin "5") (pinfunction "5_5") (pintype "bidirectional"))
      (node (ref "U$9") (pin "3") (pinfunction "3_3") (pintype "bidirectional"))
    )
    (net (code "32") (name "GPOINSIDE6") (class "Default")
      (node (ref "IC1") (pin "13") (pinfunction "O6_13") (pintype "open_collector"))
      (node (ref "K6") (pin "16") (pinfunction "2_16") (pintype "passive"))
      (node (ref "LED23") (pin "K") (pinfunction "C_K") (pintype "passive"))
      (node (ref "LED31") (pin "K") (pinfunction "C_K") (pintype "passive"))
      (node (ref "U$12") (pin "7") (pinfunction "7_7") (pintype "bidirectional"))
      (node (ref "U$6") (pin "8") (pinfunction "8_8") (pintype "bidirectional"))
      (node (ref "U$8") (pin "6") (pinfunction "6_6") (pintype "bidirectional"))
      (node (ref "U$9") (pin "4") (pinfunction "4_4") (pintype "bidirectional"))
    )
    (net (code "33") (name "GPOINSIDE7") (class "Default")
      (node (ref "IC1") (pin "12") (pinfunction "O7_12") (pintype "open_collector"))
      (node (ref "K7") (pin "16") (pinfunction "2_16") (pintype "passive"))
      (node (ref "LED24") (pin "K") (pinfunction "C_K") (pintype "passive"))
      (node (ref "LED32") (pin "K") (pinfunction "C_K") (pintype "passive"))
      (node (ref "U$10") (pin "3") (pinfunction "3_3") (pintype "bidirectional"))
      (node (ref "U$13") (pin "3") (pinfunction "3_3") (pintype "bidirectional"))
      (node (ref "U$8") (pin "7") (pinfunction "7_7") (pintype "bidirectional"))
      (node (ref "U$9") (pin "5") (pinfunction "5_5") (pintype "bidirectional"))
    )
    (net (code "34") (name "GPOINSIDE8") (class "Default")
      (node (ref "IC1") (pin "11") (pinfunction "O8_11") (pintype "open_collector"))
      (node (ref "K8") (pin "16") (pinfunction "2_16") (pintype "passive"))
      (node (ref "LED25") (pin "K") (pinfunction "C_K") (pintype "passive"))
      (node (ref "LED33") (pin "K") (pinfunction "C_K") (pintype "passive"))
      (node (ref "U$10") (pin "4") (pinfunction "4_4") (pintype "bidirectional"))
      (node (ref "U$13") (pin "5") (pinfunction "5_5") (pintype "bidirectional"))
      (node (ref "U$8") (pin "8") (pinfunction "8_8") (pintype "bidirectional"))
      (node (ref "U$9") (pin "6") (pinfunction "6_6") (pintype "bidirectional"))
    )
    (net (code "35") (name "I2C_SCL") (class "Default")
      (node (ref "IC2") (pin "12") (pinfunction "SCL_12") (pintype "input"))
      (node (ref "JP4") (pin "2") (pinfunction "2_2") (pintype "passive"))
      (node (ref "R2") (pin "1") (pinfunction "1_1") (pintype "passive"))
      (node (ref "SERIAL") (pin "4") (pinfunction "4_4") (pintype "passive"))
    )
    (net (code "36") (name "I2C_SDA") (class "Default")
      (node (ref "IC2") (pin "13") (pinfunction "SDA_13") (pintype "bidirectional"))
      (node (ref "JP4") (pin "1") (pinfunction "1_1") (pintype "passive"))
      (node (ref "R1") (pin "1") (pinfunction "1_1") (pintype "passive"))
      (node (ref "SERIAL") (pin "3") (pinfunction "3_3") (pintype "passive"))
    )
    (net (code "37") (name "IN1") (class "Default")
      (node (ref "IC2") (pin "21") (pinfunction "GPA0_21") (pintype "bidirectional"))
      (node (ref "LED1") (pin "K") (pinfunction "C_K") (pintype "passive"))
      (node (ref "OK1") (pin "8") (pinfunction "COL_8") (pintype "passive"))
    )
    (net (code "38") (name "IN2") (class "Default")
      (node (ref "IC2") (pin "22") (pinfunction "GPA1_22") (pintype "bidirectional"))
      (node (ref "LED2") (pin "K") (pinfunction "C_K") (pintype "passive"))
      (node (ref "OK1") (pin "6") (pinfunction "COL_6") (pintype "passive"))
    )
    (net (code "39") (name "IN3") (class "Default")
      (node (ref "IC2") (pin "23") (pinfunction "GPA2_23") (pintype "bidirectional"))
      (node (ref "LED3") (pin "K") (pinfunction "C_K") (pintype "passive"))
      (node (ref "OK2") (pin "8") (pinfunction "COL_8") (pintype "passive"))
    )
    (net (code "40") (name "IN4") (class "Default")
      (node (ref "IC2") (pin "24") (pinfunction "GPA3_24") (pintype "bidirectional"))
      (node (ref "LED4") (pin "K") (pinfunction "C_K") (pintype "passive"))
      (node (ref "OK2") (pin "6") (pinfunction "COL_6") (pintype "passive"))
    )
    (net (code "41") (name "IN5") (class "Default")
      (node (ref "IC2") (pin "25") (pinfunction "GPA4_25") (pintype "bidirectional"))
      (node (ref "LED5") (pin "K") (pinfunction "C_K") (pintype "passive"))
      (node (ref "OK3") (pin "8") (pinfunction "COL_8") (pintype "passive"))
    )
    (net (code "42") (name "IN6") (class "Default")
      (node (ref "IC2") (pin "26") (pinfunction "GPA5_26") (pintype "bidirectional"))
      (node (ref "LED6") (pin "K") (pinfunction "C_K") (pintype "passive"))
      (node (ref "OK3") (pin "6") (pinfunction "COL_6") (pintype "passive"))
    )
    (net (code "43") (name "IN7") (class "Default")
      (node (ref "IC2") (pin "27") (pinfunction "GPA6_27") (pintype "bidirectional"))
      (node (ref "LED7") (pin "K") (pinfunction "C_K") (pintype "passive"))
      (node (ref "OK4") (pin "8") (pinfunction "COL_8") (pintype "passive"))
    )
    (net (code "44") (name "IN8") (class "Default")
      (node (ref "IC2") (pin "28") (pinfunction "GPA7_28") (pintype "bidirectional"))
      (node (ref "LED8") (pin "K") (pinfunction "C_K") (pintype "passive"))
      (node (ref "OK4") (pin "6") (pinfunction "COL_6") (pintype "passive"))
    )
    (net (code "45") (name "Net-(IC1-I1)") (class "Default")
      (node (ref "IC1") (pin "1") (pinfunction "I1_1") (pintype "input"))
      (node (ref "IC2") (pin "1") (pinfunction "GPB0_1") (pintype "bidirectional"))
    )
    (net (code "46") (name "Net-(IC1-I2)") (class "Default")
      (node (ref "IC1") (pin "2") (pinfunction "I2_2") (pintype "input"))
      (node (ref "IC2") (pin "2") (pinfunction "GPB1_2") (pintype "bidirectional"))
    )
    (net (code "47") (name "Net-(IC1-I3)") (class "Default")
      (node (ref "IC1") (pin "3") (pinfunction "I3_3") (pintype "input"))
      (node (ref "IC2") (pin "3") (pinfunction "GPB2_3") (pintype "bidirectional"))
    )
    (net (code "48") (name "Net-(IC1-I4)") (class "Default")
      (node (ref "IC1") (pin "4") (pinfunction "I4_4") (pintype "input"))
      (node (ref "IC2") (pin "4") (pinfunction "GPB3_4") (pintype "bidirectional"))
    )
    (net (code "49") (name "Net-(IC1-I5)") (class "Default")
      (node (ref "IC1") (pin "5") (pinfunction "I5_5") (pintype "input"))
      (node (ref "IC2") (pin "5") (pinfunction "GPB4_5") (pintype "bidirectional"))
    )
    (net (code "50") (name "Net-(IC1-I6)") (class "Default")
      (node (ref "IC1") (pin "6") (pinfunction "I6_6") (pintype "input"))
      (node (ref "IC2") (pin "6") (pinfunction "GPB5_6") (pintype "bidirectional"))
    )
    (net (code "51") (name "Net-(IC1-I7)") (class "Default")
      (node (ref "IC1") (pin "7") (pinfunction "I7_7") (pintype "input"))
      (node (ref "IC2") (pin "7") (pinfunction "GPB6_7") (pintype "bidirectional"))
    )
    (net (code "52") (name "Net-(IC1-I8)") (class "Default")
      (node (ref "IC1") (pin "8") (pinfunction "I8_8") (pintype "input"))
      (node (ref "IC2") (pin "8") (pinfunction "GPB7_8") (pintype "bidirectional"))
    )
    (net (code "53") (name "Net-(JP3-Pad2)") (class "Default")
      (node (ref "JP3") (pin "2") (pinfunction "2_2") (pintype "passive"))
      (node (ref "JP5") (pin "2") (pinfunction "2_2") (pintype "passive"))
    )
    (net (code "54") (name "Net-(JP3-Pad4)") (class "Default")
      (node (ref "JP3") (pin "4") (pinfunction "4_4") (pintype "passive"))
      (node (ref "JP5") (pin "4") (pinfunction "4_4") (pintype "passive"))
    )
    (net (code "55") (name "Net-(JP3-Pad5)") (class "Default")
      (node (ref "JP3") (pin "5") (pinfunction "5_5") (pintype "passive"))
      (node (ref "JP5") (pin "5") (pinfunction "5_5") (pintype "passive"))
    )
    (net (code "56") (name "Net-(JP3-Pad6)") (class "Default")
      (node (ref "JP3") (pin "6") (pinfunction "6_6") (pintype "passive"))
      (node (ref "JP5") (pin "6") (pinfunction "6_6") (pintype "passive"))
    )
    (net (code "57") (name "Net-(LED1-PadA)") (class "Default")
      (node (ref "LED1") (pin "A") (pinfunction "A_A") (pintype "passive"))
      (node (ref "RN1") (pin "2") (pinfunction "2_2") (pintype "passive"))
    )
    (net (code "58") (name "Net-(LED2-PadA)") (class "Default")
      (node (ref "LED2") (pin "A") (pinfunction "A_A") (pintype "passive"))
      (node (ref "RN1") (pin "3") (pinfunction "3_3") (pintype "passive"))
    )
    (net (code "59") (name "Net-(LED3-PadA)") (class "Default")
      (node (ref "LED3") (pin "A") (pinfunction "A_A") (pintype "passive"))
      (node (ref "RN1") (pin "4") (pinfunction "4_4") (pintype "passive"))
    )
    (net (code "60") (name "Net-(LED4-PadA)") (class "Default")
      (node (ref "LED4") (pin "A") (pinfunction "A_A") (pintype "passive"))
      (node (ref "RN1") (pin "5") (pinfunction "5_5") (pintype "passive"))
    )
    (net (code "61") (name "Net-(LED5-PadA)") (class "Default")
      (node (ref "LED5") (pin "A") (pinfunction "A_A") (pintype "passive"))
      (node (ref "RN1") (pin "6") (pinfunction "6_6") (pintype "passive"))
    )
    (net (code "62") (name "Net-(LED6-PadA)") (class "Default")
      (node (ref "LED6") (pin "A") (pinfunction "A_A") (pintype "passive"))
      (node (ref "RN1") (pin "7") (pinfunction "7_7") (pintype "passive"))
    )
    (net (code "63") (name "Net-(LED7-PadA)") (class "Default")
      (node (ref "LED7") (pin "A") (pinfunction "A_A") (pintype "passive"))
      (node (ref "RN1") (pin "8") (pinfunction "8_8") (pintype "passive"))
    )
    (net (code "64") (name "Net-(LED8-PadA)") (class "Default")
      (node (ref "LED8") (pin "A") (pinfunction "A_A") (pintype "passive"))
      (node (ref "RN1") (pin "9") (pinfunction "9_9") (pintype "passive"))
    )
    (net (code "65") (name "Net-(LED9-PadA)") (class "Default")
      (node (ref "LED9") (pin "A") (pinfunction "A_A") (pintype "passive"))
      (node (ref "RN2") (pin "2") (pinfunction "2_2") (pintype "passive"))
    )
    (net (code "66") (name "Net-(LED10-PadA)") (class "Default")
      (node (ref "LED10") (pin "A") (pinfunction "A_A") (pintype "passive"))
      (node (ref "RN2") (pin "3") (pinfunction "3_3") (pintype "passive"))
    )
    (net (code "67") (name "Net-(LED11-PadA)") (class "Default")
      (node (ref "LED11") (pin "A") (pinfunction "A_A") (pintype "passive"))
      (node (ref "RN2") (pin "4") (pinfunction "4_4") (pintype "passive"))
    )
    (net (code "68") (name "Net-(LED12-PadA)") (class "Default")
      (node (ref "LED12") (pin "A") (pinfunction "A_A") (pintype "passive"))
      (node (ref "RN2") (pin "5") (pinfunction "5_5") (pintype "passive"))
    )
    (net (code "69") (name "Net-(LED13-PadA)") (class "Default")
      (node (ref "LED13") (pin "A") (pinfunction "A_A") (pintype "passive"))
      (node (ref "RN2") (pin "6") (pinfunction "6_6") (pintype "passive"))
    )
    (net (code "70") (name "Net-(LED14-PadA)") (class "Default")
      (node (ref "LED14") (pin "A") (pinfunction "A_A") (pintype "passive"))
      (node (ref "RN2") (pin "7") (pinfunction "7_7") (pintype "passive"))
    )
    (net (code "71") (name "Net-(LED15-PadA)") (class "Default")
      (node (ref "LED15") (pin "A") (pinfunction "A_A") (pintype "passive"))
      (node (ref "RN2") (pin "8") (pinfunction "8_8") (pintype "passive"))
    )
    (net (code "72") (name "Net-(LED16-PadA)") (class "Default")
      (node (ref "LED16") (pin "A") (pinfunction "A_A") (pintype "passive"))
      (node (ref "RN2") (pin "9") (pinfunction "9_9") (pintype "passive"))
    )
    (net (code "73") (name "Net-(LED17-PadA)") (class "Default")
      (node (ref "LED17") (pin "A") (pinfunction "A_A") (pintype "passive"))
      (node (ref "R5") (pin "1") (pinfunction "1_1") (pintype "passive"))
    )
    (net (code "74") (name "Net-(LED18-PadA)") (class "Default")
      (node (ref "LED18") (pin "A") (pinfunction "A_A") (pintype "passive"))
      (node (ref "RN5") (pin "2") (pinfunction "2_2") (pintype "passive"))
    )
    (net (code "75") (name "Net-(LED19-PadA)") (class "Default")
      (node (ref "LED19") (pin "A") (pinfunction "A_A") (pintype "passive"))
      (node (ref "RN5") (pin "3") (pinfunction "3_3") (pintype "passive"))
    )
    (net (code "76") (name "Net-(LED20-PadA)") (class "Default")
      (node (ref "LED20") (pin "A") (pinfunction "A_A") (pintype "passive"))
      (node (ref "RN5") (pin "4") (pinfunction "4_4") (pintype "passive"))
    )
    (net (code "77") (name "Net-(LED21-PadA)") (class "Default")
      (node (ref "LED21") (pin "A") (pinfunction "A_A") (pintype "passive"))
      (node (ref "RN5") (pin "5") (pinfunction "5_5") (pintype "passive"))
    )
    (net (code "78") (name "Net-(LED22-PadA)") (class "Default")
      (node (ref "LED22") (pin "A") (pinfunction "A_A") (pintype "passive"))
      (node (ref "RN5") (pin "6") (pinfunction "6_6") (pintype "passive"))
    )
    (net (code "79") (name "Net-(LED23-PadA)") (class "Default")
      (node (ref "LED23") (pin "A") (pinfunction "A_A") (pintype "passive"))
      (node (ref "RN5") (pin "7") (pinfunction "7_7") (pintype "passive"))
    )
    (net (code "80") (name "Net-(LED24-PadA)") (class "Default")
      (node (ref "LED24") (pin "A") (pinfunction "A_A") (pintype "passive"))
      (node (ref "RN5") (pin "8") (pinfunction "8_8") (pintype "passive"))
    )
    (net (code "81") (name "Net-(LED25-PadA)") (class "Default")
      (node (ref "LED25") (pin "A") (pinfunction "A_A") (pintype "passive"))
      (node (ref "RN5") (pin "9") (pinfunction "9_9") (pintype "passive"))
    )
    (net (code "82") (name "Net-(LED26-PadA)") (class "Default")
      (node (ref "LED26") (pin "A") (pinfunction "A_A") (pintype "passive"))
      (node (ref "RN4") (pin "2") (pinfunction "2_2") (pintype "passive"))
    )
    (net (code "83") (name "Net-(LED27-PadA)") (class "Default")
      (node (ref "LED27") (pin "A") (pinfunction "A_A") (pintype "passive"))
      (node (ref "RN4") (pin "3") (pinfunction "3_3") (pintype "passive"))
    )
    (net (code "84") (name "Net-(LED28-PadA)") (class "Default")
      (node (ref "LED28") (pin "A") (pinfunction "A_A") (pintype "passive"))
      (node (ref "RN4") (pin "4") (pinfunction "4_4") (pintype "passive"))
    )
    (net (code "85") (name "Net-(LED29-PadA)") (class "Default")
      (node (ref "LED29") (pin "A") (pinfunction "A_A") (pintype "passive"))
      (node (ref "RN4") (pin "5") (pinfunction "5_5") (pintype "passive"))
    )
    (net (code "86") (name "Net-(LED30-PadA)") (class "Default")
      (node (ref "LED30") (pin "A") (pinfunction "A_A") (pintype "passive"))
      (node (ref "RN4") (pin "6") (pinfunction "6_6") (pintype "passive"))
    )
    (net (code "87") (name "Net-(LED31-PadA)") (class "Default")
      (node (ref "LED31") (pin "A") (pinfunction "A_A") (pintype "passive"))
      (node (ref "RN4") (pin "7") (pinfunction "7_7") (pintype "passive"))
    )
    (net (code "88") (name "Net-(LED32-PadA)") (class "Default")
      (node (ref "LED32") (pin "A") (pinfunction "A_A") (pintype "passive"))
      (node (ref "RN4") (pin "8") (pinfunction "8_8") (pintype "passive"))
    )
    (net (code "89") (name "Net-(LED33-PadA)") (class "Default")
      (node (ref "LED33") (pin "A") (pinfunction "A_A") (pintype "passive"))
      (node (ref "RN4") (pin "9") (pinfunction "9_9") (pintype "passive"))
    )
    (net (code "90") (name "Net-(OK1A-A)") (class "Default")
      (node (ref "OK1") (pin "1") (pinfunction "A_1") (pintype "passive"))
      (node (ref "RN3") (pin "2") (pinfunction "2_2") (pintype "passive"))
    )
    (net (code "91") (name "Net-(OK1B-A)") (class "Default")
      (node (ref "OK1") (pin "3") (pinfunction "A_3") (pintype "passive"))
      (node (ref "RN3") (pin "3") (pinfunction "3_3") (pintype "passive"))
    )
    (net (code "92") (name "Net-(OK2A-A)") (class "Default")
      (node (ref "OK2") (pin "1") (pinfunction "A_1") (pintype "passive"))
      (node (ref "RN3") (pin "4") (pinfunction "4_4") (pintype "passive"))
    )
    (net (code "93") (name "Net-(OK2B-A)") (class "Default")
      (node (ref "OK2") (pin "3") (pinfunction "A_3") (pintype "passive"))
      (node (ref "RN3") (pin "5") (pinfunction "5_5") (pintype "passive"))
    )
    (net (code "94") (name "Net-(OK3A-A)") (class "Default")
      (node (ref "OK3") (pin "1") (pinfunction "A_1") (pintype "passive"))
      (node (ref "RN3") (pin "6") (pinfunction "6_6") (pintype "passive"))
    )
    (net (code "95") (name "Net-(OK3B-A)") (class "Default")
      (node (ref "OK3") (pin "3") (pinfunction "A_3") (pintype "passive"))
      (node (ref "RN3") (pin "7") (pinfunction "7_7") (pintype "passive"))
    )
    (net (code "96") (name "Net-(OK4A-A)") (class "Default")
      (node (ref "OK4") (pin "1") (pinfunction "A_1") (pintype "passive"))
      (node (ref "RN3") (pin "8") (pinfunction "8_8") (pintype "passive"))
    )
    (net (code "97") (name "Net-(OK4B-A)") (class "Default")
      (node (ref "OK4") (pin "3") (pinfunction "A_3") (pintype "passive"))
      (node (ref "RN3") (pin "9") (pinfunction "9_9") (pintype "passive"))
    )
    (net (code "98") (name "Net-(U$7-P$2)") (class "Default")
      (node (ref "R4") (pin "1") (pinfunction "1_1") (pintype "passive"))
      (node (ref "U$7") (pin "A2") (pinfunction "P$2_A2") (pintype "bidirectional"))
    )
    (net (code "99") (name "Net-(U$7-P$3)") (class "Default")
      (node (ref "R3") (pin "1") (pinfunction "1_1") (pintype "passive"))
      (node (ref "U$7") (pin "A3") (pinfunction "P$3_A3") (pintype "bidirectional"))
    )
    (net (code "100") (name "O1") (class "Default")
      (node (ref "K1") (pin "S2") (pinfunction "S_S2") (pintype "passive"))
      (node (ref "LED9") (pin "K") (pinfunction "C_K") (pintype "passive"))
    )
    (net (code "101") (name "O2") (class "Default")
      (node (ref "K2") (pin "S2") (pinfunction "S_S2") (pintype "passive"))
      (node (ref "LED10") (pin "K") (pinfunction "C_K") (pintype "passive"))
    )
    (net (code "102") (name "O3") (class "Default")
      (node (ref "K3") (pin "S2") (pinfunction "S_S2") (pintype "passive"))
      (node (ref "LED11") (pin "K") (pinfunction "C_K") (pintype "passive"))
    )
    (net (code "103") (name "O4") (class "Default")
      (node (ref "K4") (pin "S2") (pinfunction "S_S2") (pintype "passive"))
      (node (ref "LED12") (pin "K") (pinfunction "C_K") (pintype "passive"))
    )
    (net (code "104") (name "O5") (class "Default")
      (node (ref "K5") (pin "S2") (pinfunction "S_S2") (pintype "passive"))
      (node (ref "LED13") (pin "K") (pinfunction "C_K") (pintype "passive"))
    )
    (net (code "105") (name "O6") (class "Default")
      (node (ref "K6") (pin "S2") (pinfunction "S_S2") (pintype "passive"))
      (node (ref "LED14") (pin "K") (pinfunction "C_K") (pintype "passive"))
    )
    (net (code "106") (name "O7") (class "Default")
      (node (ref "K7") (pin "S2") (pinfunction "S_S2") (pintype "passive"))
      (node (ref "LED15") (pin "K") (pinfunction "C_K") (pintype "passive"))
    )
    (net (code "107") (name "O8") (class "Default")
      (node (ref "K8") (pin "S2") (pinfunction "S_S2") (pintype "passive"))
      (node (ref "LED16") (pin "K") (pinfunction "C_K") (pintype "passive"))
    )
    (net (code "108") (name "RES") (class "Default")
      (node (ref "GND") (pin "RES") (pinfunction "RES_RES") (pintype "bidirectional"))
      (node (ref "RESETA") (pin "1") (pinfunction "1_1") (pintype "passive"))
    )
    (net (code "109") (name "SDI_MOSI") (class "Default")
      (node (ref "SERIAL") (pin "8") (pinfunction "8_8") (pintype "passive"))
    )
    (net (code "110") (name "SDI_SCLK") (class "Default")
      (node (ref "SERIAL") (pin "7") (pinfunction "7_7") (pintype "passive"))
    )
    (net (code "111") (name "SLIDER_IN") (class "Default")
      (node (ref "GND") (pin "A0") (pinfunction "A0_A0") (pintype "bidirectional"))
      (node (ref "SERIAL") (pin "5") (pinfunction "5_5") (pintype "passive"))
    )
    (net (code "112") (name "VIN") (class "Default")
      (node (ref "GND") (pin "VIN") (pinfunction "VIN_VIN") (pintype "bidirectional"))
    )
    (net (code "113") (name "unconnected-(GND-*D5-PadD5)") (class "Default")
      (node (ref "GND") (pin "D5") (pinfunction "*D5_D5") (pintype "bidirectional"))
    )
    (net (code "114") (name "unconnected-(GND-*D6-PadD6)") (class "Default")
      (node (ref "GND") (pin "D6") (pinfunction "*D6_D6") (pintype "bidirectional"))
    )
    (net (code "115") (name "unconnected-(GND-*D9-PadD9)") (class "Default")
      (node (ref "GND") (pin "D9") (pinfunction "*D9_D9") (pintype "bidirectional"))
    )
    (net (code "116") (name "unconnected-(GND-*D10-PadD10)") (class "Default")
      (node (ref "GND") (pin "D10") (pinfunction "*D10_D10") (pintype "bidirectional"))
    )
    (net (code "117") (name "unconnected-(GND-*D11-PadD11)") (class "Default")
      (node (ref "GND") (pin "D11") (pinfunction "*D11_D11") (pintype "bidirectional"))
    )
    (net (code "118") (name "unconnected-(GND-Pad3.3V)") (class "Default")
      (node (ref "GND") (pin "3.3V") (pinfunction "3.3V_3.3V") (pintype "bidirectional"))
    )
    (net (code "119") (name "unconnected-(GND-PadA2)") (class "Default")
      (node (ref "GND") (pin "A2") (pinfunction "A2_A2") (pintype "bidirectional"))
    )
    (net (code "120") (name "unconnected-(GND-PadA3)") (class "Default")
      (node (ref "GND") (pin "A3") (pinfunction "A3_A3") (pintype "bidirectional"))
    )
    (net (code "121") (name "unconnected-(GND-PadA4)") (class "Default")
      (node (ref "GND") (pin "A4") (pinfunction "A4_A4") (pintype "bidirectional"))
    )
    (net (code "122") (name "unconnected-(GND-PadA5)") (class "Default")
      (node (ref "GND") (pin "A5") (pinfunction "A5_A5") (pintype "bidirectional"))
    )
    (net (code "123") (name "unconnected-(GND-PadAREF)") (class "Default")
      (node (ref "GND") (pin "AREF") (pinfunction "AREF_AREF") (pintype "bidirectional"))
    )
    (net (code "124") (name "unconnected-(GND-PadD4)") (class "Default")
      (node (ref "GND") (pin "D4") (pinfunction "D4_D4") (pintype "bidirectional"))
    )
    (net (code "125") (name "unconnected-(GND-PadD8)") (class "Default")
      (node (ref "GND") (pin "D8") (pinfunction "D8_D8") (pintype "bidirectional"))
    )
    (net (code "126") (name "unconnected-(GND-PadD12)") (class "Default")
      (node (ref "GND") (pin "D12") (pinfunction "D12_D12") (pintype "bidirectional"))
    )
    (net (code "127") (name "unconnected-(GND-PadD13)") (class "Default")
      (node (ref "GND") (pin "D13") (pinfunction "D13_D13") (pintype "bidirectional"))
    )
    (net (code "128") (name "unconnected-(GND-PadRX)") (class "Default")
      (node (ref "GND") (pin "RX") (pinfunction "RX_RX") (pintype "bidirectional"))
    )
    (net (code "129") (name "unconnected-(GND-PadTX)") (class "Default")
      (node (ref "GND") (pin "TX") (pinfunction "TX_TX") (pintype "bidirectional"))
    )
    (net (code "130") (name "unconnected-(IC2-INTA-Pad20)") (class "Default")
      (node (ref "IC2") (pin "20") (pinfunction "INTA_20") (pintype "output"))
    )
    (net (code "131") (name "unconnected-(IC2-INTB-Pad19)") (class "Default")
      (node (ref "IC2") (pin "19") (pinfunction "INTB_19") (pintype "output"))
    )
    (net (code "132") (name "unconnected-(JP1-Pad1)") (class "Default")
      (node (ref "JP1") (pin "1") (pinfunction "1_1") (pintype "passive"))
    )
    (net (code "133") (name "unconnected-(JP1-Pad2)") (class "Default")
      (node (ref "JP1") (pin "2") (pinfunction "2_2") (pintype "passive"))
    )
    (net (code "134") (name "unconnected-(K1B-O-PadO1)") (class "Default")
      (node (ref "K1") (pin "O1") (pinfunction "O_O1") (pintype "passive"))
    )
    (net (code "135") (name "unconnected-(K1C-O-PadO2)") (class "Default")
      (node (ref "K1") (pin "O2") (pinfunction "O_O2") (pintype "passive"))
    )
    (net (code "136") (name "unconnected-(K2B-O-PadO1)") (class "Default")
      (node (ref "K2") (pin "O1") (pinfunction "O_O1") (pintype "passive"))
    )
    (net (code "137") (name "unconnected-(K2C-O-PadO2)") (class "Default")
      (node (ref "K2") (pin "O2") (pinfunction "O_O2") (pintype "passive"))
    )
    (net (code "138") (name "unconnected-(K3B-O-PadO1)") (class "Default")
      (node (ref "K3") (pin "O1") (pinfunction "O_O1") (pintype "passive"))
    )
    (net (code "139") (name "unconnected-(K3C-O-PadO2)") (class "Default")
      (node (ref "K3") (pin "O2") (pinfunction "O_O2") (pintype "passive"))
    )
    (net (code "140") (name "unconnected-(K4B-O-PadO1)") (class "Default")
      (node (ref "K4") (pin "O1") (pinfunction "O_O1") (pintype "passive"))
    )
    (net (code "141") (name "unconnected-(K4C-O-PadO2)") (class "Default")
      (node (ref "K4") (pin "O2") (pinfunction "O_O2") (pintype "passive"))
    )
    (net (code "142") (name "unconnected-(K5B-O-PadO1)") (class "Default")
      (node (ref "K5") (pin "O1") (pinfunction "O_O1") (pintype "passive"))
    )
    (net (code "143") (name "unconnected-(K5C-O-PadO2)") (class "Default")
      (node (ref "K5") (pin "O2") (pinfunction "O_O2") (pintype "passive"))
    )
    (net (code "144") (name "unconnected-(K6B-O-PadO1)") (class "Default")
      (node (ref "K6") (pin "O1") (pinfunction "O_O1") (pintype "passive"))
    )
    (net (code "145") (name "unconnected-(K6C-O-PadO2)") (class "Default")
      (node (ref "K6") (pin "O2") (pinfunction "O_O2") (pintype "passive"))
    )
    (net (code "146") (name "unconnected-(K7B-O-PadO1)") (class "Default")
      (node (ref "K7") (pin "O1") (pinfunction "O_O1") (pintype "passive"))
    )
    (net (code "147") (name "unconnected-(K7C-O-PadO2)") (class "Default")
      (node (ref "K7") (pin "O2") (pinfunction "O_O2") (pintype "passive"))
    )
    (net (code "148") (name "unconnected-(K8B-O-PadO1)") (class "Default")
      (node (ref "K8") (pin "O1") (pinfunction "O_O1") (pintype "passive"))
    )
    (net (code "149") (name "unconnected-(K8C-O-PadO2)") (class "Default")
      (node (ref "K8") (pin "O2") (pinfunction "O_O2") (pintype "passive"))
    )
    (net (code "150") (name "unconnected-(U$11-Pad4)") (class "Default")
      (node (ref "U$11") (pin "4") (pinfunction "4_4") (pintype "bidirectional"))
    )
    (net (code "151") (name "unconnected-(U$11-Pad6)") (class "Default")
      (node (ref "U$11") (pin "6") (pinfunction "6_6") (pintype "bidirectional"))
    )
    (net (code "152") (name "unconnected-(U$11-Pad8)") (class "Default")
      (node (ref "U$11") (pin "8") (pinfunction "8_8") (pintype "bidirectional"))
    )
    (net (code "153") (name "unconnected-(U$12-Pad4)") (class "Default")
      (node (ref "U$12") (pin "4") (pinfunction "4_4") (pintype "bidirectional"))
    )
    (net (code "154") (name "unconnected-(U$12-Pad6)") (class "Default")
      (node (ref "U$12") (pin "6") (pinfunction "6_6") (pintype "bidirectional"))
    )
    (net (code "155") (name "unconnected-(U$12-Pad8)") (class "Default")
      (node (ref "U$12") (pin "8") (pinfunction "8_8") (pintype "bidirectional"))
    )
    (net (code "156") (name "unconnected-(U$13-Pad4)") (class "Default")
      (node (ref "U$13") (pin "4") (pinfunction "4_4") (pintype "bidirectional"))
    )
    (net (code "157") (name "unconnected-(U$13-Pad6)") (class "Default")
      (node (ref "U$13") (pin "6") (pinfunction "6_6") (pintype "bidirectional"))
    )
    (net (code "158") (name "unconnected-(U$13-Pad7)") (class "Default")
      (node (ref "U$13") (pin "7") (pinfunction "7_7") (pintype "bidirectional"))
    )
    (net (code "159") (name "unconnected-(U$13-Pad8)") (class "Default")
      (node (ref "U$13") (pin "8") (pinfunction "8_8") (pintype "bidirectional"))
    )
  )
)
